# GPS.net
KiCad netlist of a schematic drawn in Altium Designer
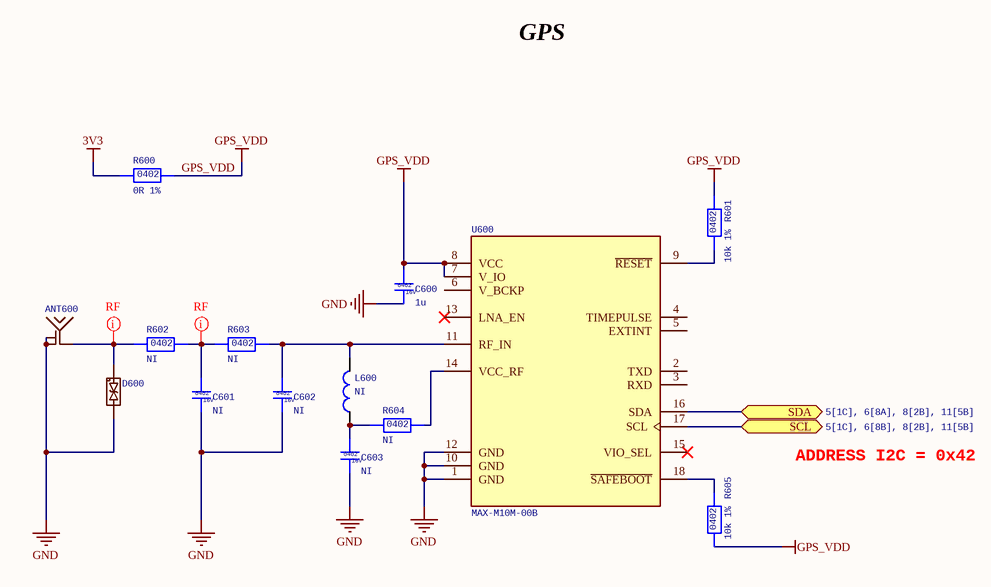
[diagram p0: GPS.SchDoc]

(export (version "E")
  (design (tool "Eeschema 10.0.6"))
  (components
    (comp (ref "ANT600")
      (value "2337019-1")
      (footprint "2337019-1")
      (description "UMCC MICRO-COAX RECEPTACLE, GEN")
      (libsource (lib "Hw_Lib") (part "2337019-1"))
    )
    (comp (ref "C600")
      (value "1u")
      (footprint "CAP0402")
      (fields
        (field (name "MANUFACTURER") "Taiyo Yuden")
        (field (name "MANUFACTURER PART NUMBER") "EMK105BJ105KV-F")
      )
      (libsource (lib "Hw_Lib") (part "C_0402_1u"))
    )
    (comp (ref "C601")
      (value "NI")
      (footprint "CAP0402")
      (fields
        (field (name "MANUFACTURER") "Murata")
        (field (name "MANUFACTURER PART NUMBER") "GRM155R71C104KA88J")
      )
      (libsource (lib "Hw_Lib") (part "C_0402_0.1u"))
    )
    (comp (ref "C602")
      (value "NI")
      (footprint "CAP0402")
      (fields
        (field (name "MANUFACTURER") "Murata")
        (field (name "MANUFACTURER PART NUMBER") "GRM155R71C104KA88J")
      )
      (libsource (lib "Hw_Lib") (part "C_0402_0.1u"))
    )
    (comp (ref "C603")
      (value "NI")
      (footprint "CAP0402")
      (fields
        (field (name "MANUFACTURER") "Murata")
        (field (name "MANUFACTURER PART NUMBER") "GRM155R71C104KA88J")
      )
      (libsource (lib "Hw_Lib") (part "C_0402_0.1u"))
    )
    (comp (ref "D600")
      (value "DESD3V3S1BL-7B")
      (footprint "DESD3V3S1BL-7B")
      (description "Trans Voltage Suppressor Diode, 35W, 3.3V V(RWM), Bidirectional, 1 Element, Silicon")
      (fields (field (name "MANUFACTURER") "Diodes"))
      (libsource (lib "Hw_Lib") (part "DESD3V3S1BL-7B"))
    )
    (comp (ref "L600")
      (value "NI")
      (footprint "0402(1005)")
      (description "General Purpose Inductor, 2.7uH, 10%, 1 Element, Ferrite-Core, SMD, 0402")
      (fields
        (field (name "MANUFACTURER") "Abracon")
        (field (name "MANUFACTURER PART NUMBER") "AIML-0402-2R7K-T")
      )
      (libsource (lib "Hw_Lib") (part "Inductor 3.3u"))
    )
    (comp (ref "R600")
      (value "0R 1%")
      (footprint "RES0402")
      (description "Metal Glaze/thick Film, 0.0625W, 0ohm, Surface Mount, 0402")
      (fields
        (field (name "MANUFACTURER") "Yageo")
        (field (name "MANUFACTURER PART NUMBER") "RC0402JR-070RL")
      )
      (libsource (lib "Hw_Lib") (part "R_0402_0R"))
    )
    (comp (ref "R601")
      (value "10k 1%")
      (footprint "R0402")
      (fields
        (field (name "MANUFACTURER") "Samsung")
        (field (name "MANUFACTURER PART NUMBER") "RC1005F103CS")
        (field (name "TOLERANCE") "1%")
      )
      (libsource (lib "Hw_Lib") (part "R_0402_10k"))
    )
    (comp (ref "R602")
      (value "NI")
      (footprint "RES0402")
      (description "Metal Glaze/thick Film, 0.0625W, 0ohm, Surface Mount, 0402")
      (fields
        (field (name "MANUFACTURER") "Yageo")
        (field (name "MANUFACTURER PART NUMBER") "RC0402JR-070RL")
      )
      (libsource (lib "Hw_Lib") (part "R_0402_0R"))
    )
    (comp (ref "R603")
      (value "NI")
      (footprint "RES0402")
      (description "Metal Glaze/thick Film, 0.0625W, 0ohm, Surface Mount, 0402")
      (fields
        (field (name "MANUFACTURER") "Yageo")
        (field (name "MANUFACTURER PART NUMBER") "RC0402JR-070RL")
      )
      (libsource (lib "Hw_Lib") (part "R_0402_0R"))
    )
    (comp (ref "R604")
      (value "NI")
      (footprint "RES0402")
      (description "Metal Glaze/thick Film, 0.0625W, 0ohm, Surface Mount, 0402")
      (fields
        (field (name "MANUFACTURER") "Yageo")
        (field (name "MANUFACTURER PART NUMBER") "RC0402JR-070RL")
      )
      (libsource (lib "Hw_Lib") (part "R_0402_0R"))
    )
    (comp (ref "R605")
      (value "10k 1%")
      (footprint "R0402")
      (fields
        (field (name "MANUFACTURER") "Samsung")
        (field (name "MANUFACTURER PART NUMBER") "RC1005F103CS")
        (field (name "TOLERANCE") "1%")
      )
      (libsource (lib "Hw_Lib") (part "R_0402_10k"))
    )
    (comp (ref "U600")
      (value "MAX-M10M-00B")
      (footprint "MAX-M10M-00B")
      (description "Gnss Lcc Rx Mod, Rom, Crystal")
      (fields (field (name "MANUFACTURER") "u-blox"))
      (libsource (lib "Hw_Lib") (part "MAX-M10M-00B"))
    )
  )
  (nets
    (net (code "1") (name "/SCL") (class "Default")
      (node (ref "U600") (pin "17") (pinfunction "SCL_17") (pintype "open_collector"))
    )
    (net (code "2") (name "/SDA") (class "Default")
      (node (ref "U600") (pin "16") (pinfunction "SDA_16") (pintype "open_collector"))
    )
    (net (code "3") (name "3V3") (class "Default")
      (node (ref "R600") (pin "1") (pinfunction "1_1") (pintype "passive"))
    )
    (net (code "4") (name "GND") (class "Default")
      (node (ref "ANT600") (pin "G1") (pinfunction "GND_G1") (pintype "open_collector"))
      (node (ref "ANT600") (pin "G2") (pinfunction "GND_G2") (pintype "open_collector"))
      (node (ref "C600") (pin "2") (pinfunction "2_2") (pintype "passive"))
      (node (ref "C601") (pin "2") (pinfunction "2_2") (pintype "passive"))
      (node (ref "C602") (pin "2") (pinfunction "2_2") (pintype "passive"))
      (node (ref "C603") (pin "2") (pinfunction "2_2") (pintype "passive"))
      (node (ref "D600") (pin "2") (pinfunction "2_2") (pintype "passive"))
      (node (ref "U600") (pin "1") (pinfunction "GND_1") (pintype "open_collector"))
      (node (ref "U600") (pin "10") (pinfunction "GND_10") (pintype "open_collector"))
      (node (ref "U600") (pin "12") (pinfunction "GND_12") (pintype "open_collector"))
    )
    (net (code "5") (name "GPS_VDD") (class "Default")
      (node (ref "C600") (pin "1") (pinfunction "1_1") (pintype "passive"))
      (node (ref "R600") (pin "2") (pinfunction "2_2") (pintype "passive"))
      (node (ref "R601") (pin "2") (pinfunction "2_2") (pintype "passive"))
      (node (ref "R605") (pin "1") (pinfunction "1_1") (pintype "passive"))
      (node (ref "U600") (pin "7") (pinfunction "V_IO_7") (pintype "open_collector"))
      (node (ref "U600") (pin "8") (pinfunction "VCC_8") (pintype "open_collector"))
    )
    (net (code "6") (name "Net-(ANT600-Pad1)") (class "Default")
      (node (ref "ANT600") (pin "1") (pinfunction "1_1") (pintype "passive"))
      (node (ref "D600") (pin "1") (pinfunction "1_1") (pintype "passive"))
      (node (ref "R602") (pin "1") (pinfunction "1_1") (pintype "passive"))
    )
    (net (code "7") (name "Net-(C601-Pad1)") (class "Default")
      (node (ref "C601") (pin "1") (pinfunction "1_1") (pintype "passive"))
      (node (ref "R602") (pin "2") (pinfunction "2_2") (pintype "passive"))
      (node (ref "R603") (pin "1") (pinfunction "1_1") (pintype "passive"))
    )
    (net (code "8") (name "Net-(C603-Pad1)") (class "Default")
      (node (ref "C603") (pin "1") (pinfunction "1_1") (pintype "passive"))
      (node (ref "L600") (pin "1") (pinfunction "1_1") (pintype "passive"))
      (node (ref "R604") (pin "1") (pinfunction "1_1") (pintype "passive"))
    )
    (net (code "9") (name "Net-(U600-RF_IN)") (class "Default")
      (node (ref "C602") (pin "1") (pinfunction "1_1") (pintype "passive"))
      (node (ref "L600") (pin "2") (pinfunction "2_2") (pintype "passive"))
      (node (ref "R603") (pin "2") (pinfunction "2_2") (pintype "passive"))
      (node (ref "U600") (pin "11") (pinfunction "RF_IN_11") (pintype "open_collector"))
    )
    (net (code "10") (name "Net-(U600-VCC_RF)") (class "Default")
      (node (ref "R604") (pin "2") (pinfunction "2_2") (pintype "passive"))
      (node (ref "U600") (pin "14") (pinfunction "VCC_RF_14") (pintype "open_collector"))
    )
    (net (code "11") (name "Net-(U600-~{RESET})") (class "Default")
      (node (ref "R601") (pin "1") (pinfunction "1_1") (pintype "passive"))
      (node (ref "U600") (pin "9") (pinfunction "~{RESET}_9") (pintype "open_collector"))
    )
    (net (code "12") (name "Net-(U600-~{SAFEBOOT})") (class "Default")
      (node (ref "R605") (pin "2") (pinfunction "2_2") (pintype "passive"))
      (node (ref "U600") (pin "18") (pinfunction "~{SAFEBOOT}_18") (pintype "open_collector"))
    )
    (net (code "13") (name "unconnected-(U600-EXTINT-Pad5)") (class "Default")
      (node (ref "U600") (pin "5") (pinfunction "EXTINT_5") (pintype "open_collector"))
    )
    (net (code "14") (name "unconnected-(U600-LNA_EN-Pad13)") (class "Default")
      (node (ref "U600") (pin "13") (pinfunction "LNA_EN_13") (pintype "open_collector+no_connect"))
    )
    (net (code "15") (name "unconnected-(U600-RXD-Pad3)") (class "Default")
      (node (ref "U600") (pin "3") (pinfunction "RXD_3") (pintype "open_collector"))
    )
    (net (code "16") (name "unconnected-(U600-TIMEPULSE-Pad4)") (class "Default")
      (node (ref "U600") (pin "4") (pinfunction "TIMEPULSE_4") (pintype "open_collector"))
    )
    (net (code "17") (name "unconnected-(U600-TXD-Pad2)") (class "Default")
      (node (ref "U600") (pin "2") (pinfunction "TXD_2") (pintype "open_collector"))
    )
    (net (code "18") (name "unconnected-(U600-VIO_SEL-Pad15)") (class "Default")
      (node (ref "U600") (pin "15") (pinfunction "VIO_SEL_15") (pintype "open_collector+no_connect"))
    )
    (net (code "19") (name "unconnected-(U600-V_BCKP-Pad6)") (class "Default")
      (node (ref "U600") (pin "6") (pinfunction "V_BCKP_6") (pintype "open_collector"))
    )
  )
)
